# G879X.net
KiCad netlist of a schematic drawn in EAGLE
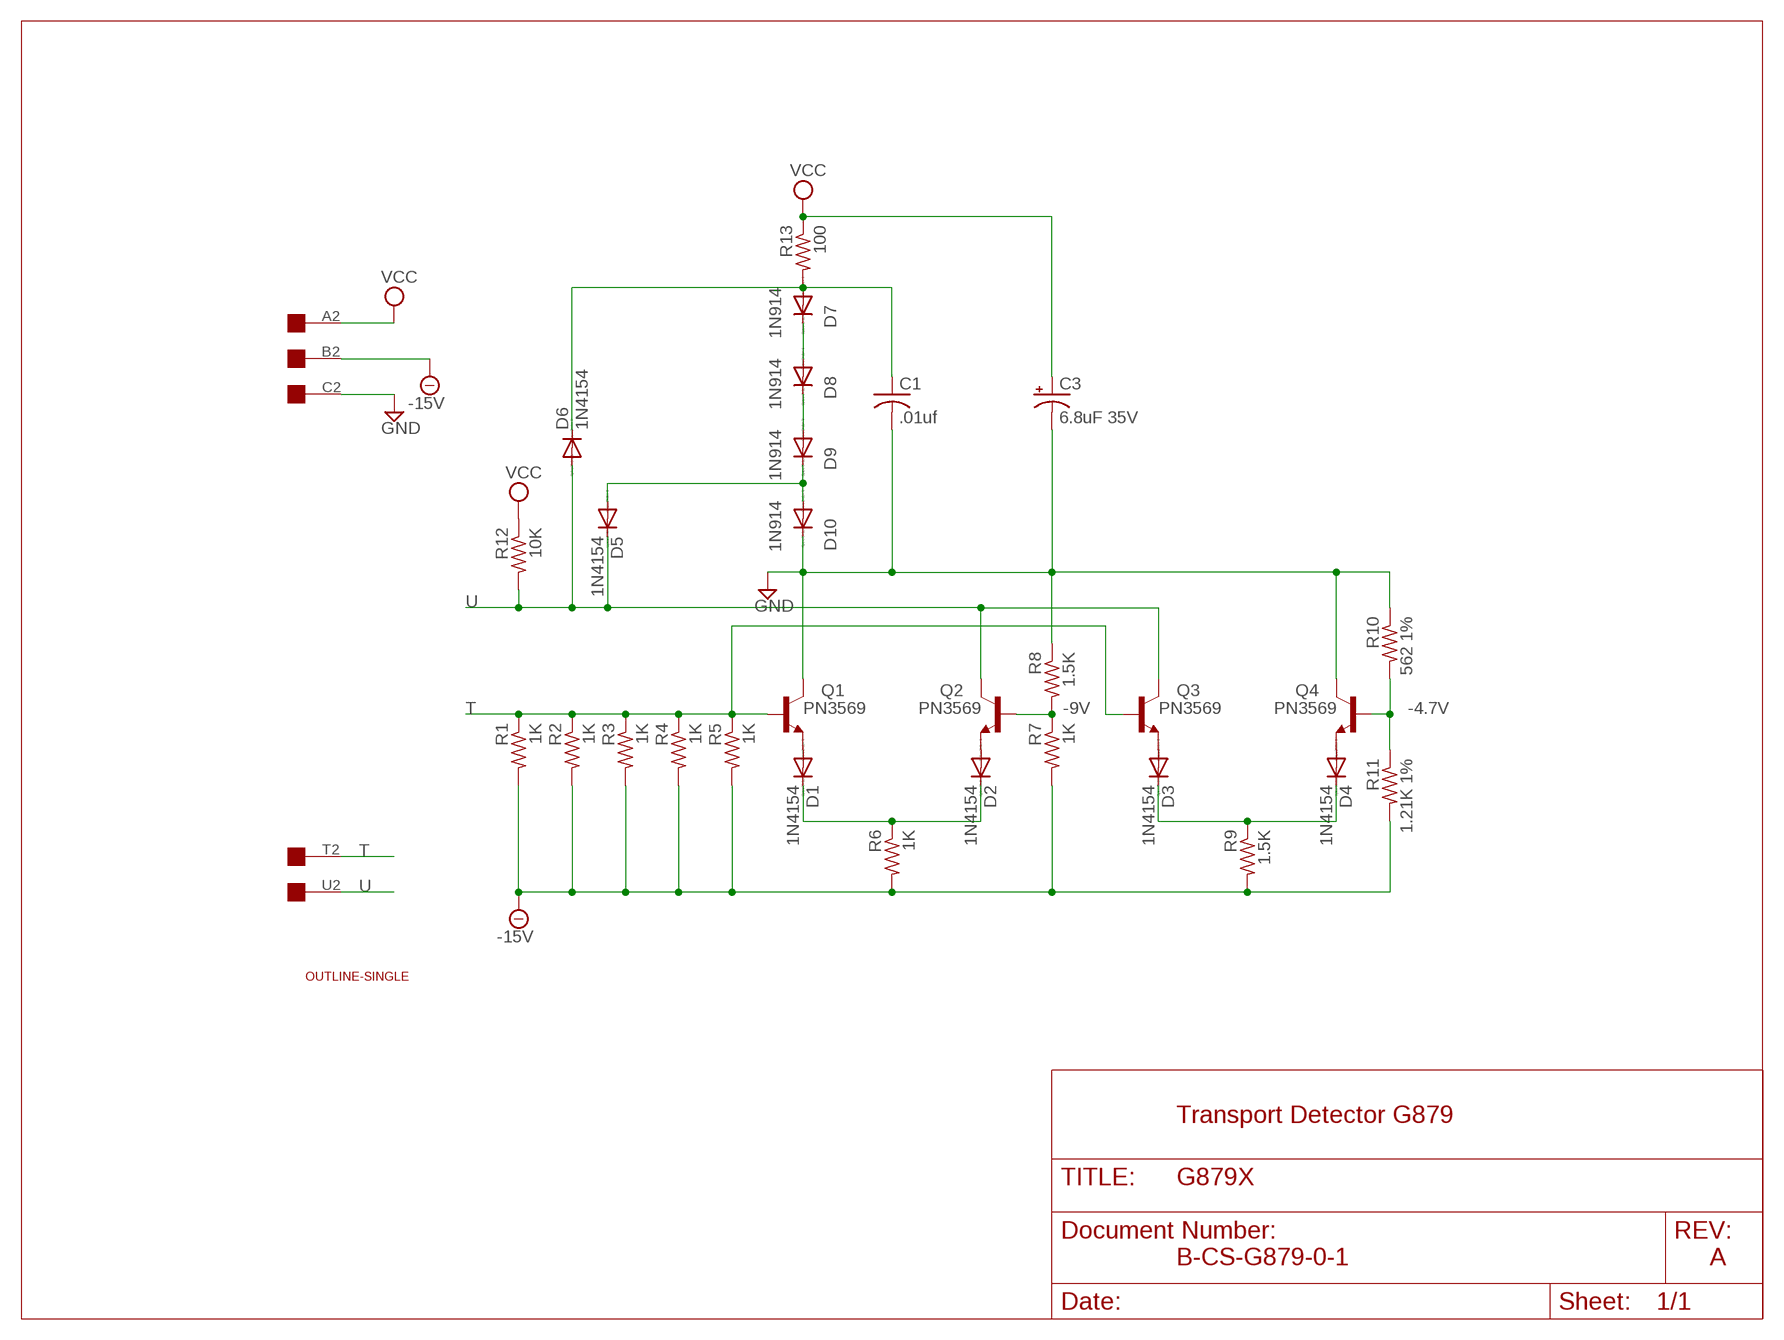
[diagram p0: schematic, sheet 1]

(export (version "E")
  (design (tool "Eeschema 10.0.6"))
  (components
    (comp (ref "C1")
      (value ".01uf")
      (footprint "eagle-import:C050-025X075")
      (libsource (lib "eagle-import") (part "C-US050-025X075"))
    )
    (comp (ref "C3")
      (value "6.8uF 35V")
      (footprint "eagle-import:E12-8")
      (libsource (lib "eagle-import") (part "CPOL-USE20-8AXIAL"))
    )
    (comp (ref "D1")
      (value "1N4154")
      (footprint "eagle-import:DO41-10")
      (libsource (lib "eagle-import") (part "1N4004"))
    )
    (comp (ref "D2")
      (value "1N4154")
      (footprint "eagle-import:DO41-10")
      (libsource (lib "eagle-import") (part "1N4004"))
    )
    (comp (ref "D3")
      (value "1N4154")
      (footprint "eagle-import:DO41-10")
      (libsource (lib "eagle-import") (part "1N4004"))
    )
    (comp (ref "D4")
      (value "1N4154")
      (footprint "eagle-import:DO41-10")
      (libsource (lib "eagle-import") (part "1N4004"))
    )
    (comp (ref "D5")
      (value "1N4154")
      (footprint "eagle-import:DO41-10")
      (libsource (lib "eagle-import") (part "1N4004"))
    )
    (comp (ref "D6")
      (value "1N4154")
      (footprint "eagle-import:DO41-10")
      (libsource (lib "eagle-import") (part "1N4004"))
    )
    (comp (ref "D7")
      (value "1N914")
      (footprint "eagle-import:DO41-10")
      (libsource (lib "eagle-import") (part "1N4004"))
    )
    (comp (ref "D8")
      (value "1N914")
      (footprint "eagle-import:DO41-10")
      (libsource (lib "eagle-import") (part "1N4004"))
    )
    (comp (ref "D9")
      (value "1N914")
      (footprint "eagle-import:DO41-10")
      (libsource (lib "eagle-import") (part "1N4004"))
    )
    (comp (ref "D10")
      (value "1N914")
      (footprint "eagle-import:DO41-10")
      (libsource (lib "eagle-import") (part "1N4004"))
    )
    (comp (ref "Q1")
      (value "PN3569")
      (footprint "eagle-import:TO39")
      (libsource (lib "eagle-import") (part "2N1711"))
    )
    (comp (ref "Q2")
      (value "PN3569")
      (footprint "eagle-import:TO39")
      (libsource (lib "eagle-import") (part "2N1711"))
    )
    (comp (ref "Q3")
      (value "PN3569")
      (footprint "eagle-import:TO39")
      (libsource (lib "eagle-import") (part "2N1711"))
    )
    (comp (ref "Q4")
      (value "PN3569")
      (footprint "eagle-import:TO39")
      (libsource (lib "eagle-import") (part "2N1711"))
    )
    (comp (ref "R1")
      (value "1K")
      (footprint "eagle-import:0207_10")
      (libsource (lib "eagle-import") (part "R-US_0207/10"))
    )
    (comp (ref "R2")
      (value "1K")
      (footprint "eagle-import:0207_10")
      (libsource (lib "eagle-import") (part "R-US_0207/10"))
    )
    (comp (ref "R3")
      (value "1K")
      (footprint "eagle-import:0207_10")
      (libsource (lib "eagle-import") (part "R-US_0207/10"))
    )
    (comp (ref "R4")
      (value "1K")
      (footprint "eagle-import:0207_10")
      (libsource (lib "eagle-import") (part "R-US_0207/10"))
    )
    (comp (ref "R5")
      (value "1K")
      (footprint "eagle-import:0207_10")
      (libsource (lib "eagle-import") (part "R-US_0207/10"))
    )
    (comp (ref "R6")
      (value "1K")
      (footprint "eagle-import:0207_10")
      (libsource (lib "eagle-import") (part "R-US_0207/10"))
    )
    (comp (ref "R7")
      (value "1K")
      (footprint "eagle-import:0207_10")
      (libsource (lib "eagle-import") (part "R-US_0207/10"))
    )
    (comp (ref "R8")
      (value "1.5K")
      (footprint "eagle-import:0207_10")
      (libsource (lib "eagle-import") (part "R-US_0207/10"))
    )
    (comp (ref "R9")
      (value "1.5K")
      (footprint "eagle-import:0207_10")
      (libsource (lib "eagle-import") (part "R-US_0207/10"))
    )
    (comp (ref "R10")
      (value "562 1%")
      (footprint "eagle-import:0207_15")
      (libsource (lib "eagle-import") (part "R-US_0207/15"))
    )
    (comp (ref "R11")
      (value "1.21K 1%")
      (footprint "eagle-import:0207_15")
      (libsource (lib "eagle-import") (part "R-US_0207/15"))
    )
    (comp (ref "R12")
      (value "10K")
      (footprint "eagle-import:0207_10")
      (libsource (lib "eagle-import") (part "R-US_0207/10"))
    )
    (comp (ref "R13")
      (value "100")
      (footprint "eagle-import:0207_10")
      (libsource (lib "eagle-import") (part "R-US_0207/10"))
    )
    (comp (ref "U$1")
      (value "EDGE-1")
      (footprint "eagle-import:EDGE-CON1")
      (libsource (lib "eagle-import") (part "EDGE-1"))
    )
    (comp (ref "U$2")
      (value "OUTLINE-SINGLE")
      (footprint "eagle-import:SINGLE")
      (libsource (lib "eagle-import") (part "OUTLINE-SINGLE"))
    )
  )
  (nets
    (net (code "1") (name "-15V") (class "Default")
      (node (ref "R1") (pin "2") (pinfunction "2_2") (pintype "passive"))
      (node (ref "R11") (pin "2") (pinfunction "2_2") (pintype "passive"))
      (node (ref "R2") (pin "2") (pinfunction "2_2") (pintype "passive"))
      (node (ref "R3") (pin "2") (pinfunction "2_2") (pintype "passive"))
      (node (ref "R4") (pin "2") (pinfunction "2_2") (pintype "passive"))
      (node (ref "R5") (pin "2") (pinfunction "2_2") (pintype "passive"))
      (node (ref "R6") (pin "2") (pinfunction "2_2") (pintype "passive"))
      (node (ref "R7") (pin "2") (pinfunction "2_2") (pintype "passive"))
      (node (ref "R9") (pin "2") (pinfunction "2_2") (pintype "passive"))
      (node (ref "U$1") (pin "B2") (pinfunction "1_B2") (pintype "bidirectional"))
    )
    (net (code "2") (name "/-4.7V") (class "Default")
      (node (ref "Q4") (pin "2") (pinfunction "B_2") (pintype "passive"))
      (node (ref "R10") (pin "2") (pinfunction "2_2") (pintype "passive"))
      (node (ref "R11") (pin "1") (pinfunction "1_1") (pintype "passive"))
    )
    (net (code "3") (name "/-9V") (class "Default")
      (node (ref "Q2") (pin "2") (pinfunction "B_2") (pintype "passive"))
      (node (ref "R7") (pin "1") (pinfunction "1_1") (pintype "passive"))
      (node (ref "R8") (pin "2") (pinfunction "2_2") (pintype "passive"))
    )
    (net (code "4") (name "/T") (class "Default")
      (node (ref "Q1") (pin "2") (pinfunction "B_2") (pintype "passive"))
      (node (ref "Q3") (pin "2") (pinfunction "B_2") (pintype "passive"))
      (node (ref "R1") (pin "1") (pinfunction "1_1") (pintype "passive"))
      (node (ref "R2") (pin "1") (pinfunction "1_1") (pintype "passive"))
      (node (ref "R3") (pin "1") (pinfunction "1_1") (pintype "passive"))
      (node (ref "R4") (pin "1") (pinfunction "1_1") (pintype "passive"))
      (node (ref "R5") (pin "1") (pinfunction "1_1") (pintype "passive"))
      (node (ref "U$1") (pin "T2") (pinfunction "1_T2") (pintype "bidirectional"))
    )
    (net (code "5") (name "/U") (class "Default")
      (node (ref "D5") (pin "C") (pinfunction "C_C") (pintype "passive"))
      (node (ref "D6") (pin "A") (pinfunction "A_A") (pintype "passive"))
      (node (ref "Q2") (pin "3") (pinfunction "C_3") (pintype "passive"))
      (node (ref "Q3") (pin "3") (pinfunction "C_3") (pintype "passive"))
      (node (ref "R12") (pin "2") (pinfunction "2_2") (pintype "passive"))
      (node (ref "U$1") (pin "U2") (pinfunction "1_U2") (pintype "bidirectional"))
    )
    (net (code "6") (name "GND") (class "Default")
      (node (ref "C1") (pin "2") (pinfunction "2_2") (pintype "passive"))
      (node (ref "C3") (pin "-") (pinfunction "-_-") (pintype "passive"))
      (node (ref "D10") (pin "C") (pinfunction "C_C") (pintype "passive"))
      (node (ref "Q1") (pin "3") (pinfunction "C_3") (pintype "passive"))
      (node (ref "Q4") (pin "3") (pinfunction "C_3") (pintype "passive"))
      (node (ref "R10") (pin "1") (pinfunction "1_1") (pintype "passive"))
      (node (ref "R8") (pin "1") (pinfunction "1_1") (pintype "passive"))
      (node (ref "U$1") (pin "C2") (pinfunction "1_C2") (pintype "bidirectional"))
    )
    (net (code "7") (name "Net-(C1-Pad1)") (class "Default")
      (node (ref "C1") (pin "1") (pinfunction "1_1") (pintype "passive"))
      (node (ref "D6") (pin "C") (pinfunction "C_C") (pintype "passive"))
      (node (ref "D7") (pin "A") (pinfunction "A_A") (pintype "passive"))
      (node (ref "R13") (pin "2") (pinfunction "2_2") (pintype "passive"))
    )
    (net (code "8") (name "Net-(D1-PadC)") (class "Default")
      (node (ref "D1") (pin "C") (pinfunction "C_C") (pintype "passive"))
      (node (ref "D2") (pin "C") (pinfunction "C_C") (pintype "passive"))
      (node (ref "R6") (pin "1") (pinfunction "1_1") (pintype "passive"))
    )
    (net (code "9") (name "Net-(D3-PadC)") (class "Default")
      (node (ref "D3") (pin "C") (pinfunction "C_C") (pintype "passive"))
      (node (ref "D4") (pin "C") (pinfunction "C_C") (pintype "passive"))
      (node (ref "R9") (pin "1") (pinfunction "1_1") (pintype "passive"))
    )
    (net (code "10") (name "Net-(D7-PadC)") (class "Default")
      (node (ref "D7") (pin "C") (pinfunction "C_C") (pintype "passive"))
      (node (ref "D8") (pin "A") (pinfunction "A_A") (pintype "passive"))
    )
    (net (code "11") (name "Net-(D8-PadC)") (class "Default")
      (node (ref "D8") (pin "C") (pinfunction "C_C") (pintype "passive"))
      (node (ref "D9") (pin "A") (pinfunction "A_A") (pintype "passive"))
    )
    (net (code "12") (name "Net-(D10-PadA)") (class "Default")
      (node (ref "D10") (pin "A") (pinfunction "A_A") (pintype "passive"))
      (node (ref "D5") (pin "A") (pinfunction "A_A") (pintype "passive"))
      (node (ref "D9") (pin "C") (pinfunction "C_C") (pintype "passive"))
    )
    (net (code "13") (name "Net-(Q1-E)") (class "Default")
      (node (ref "D1") (pin "A") (pinfunction "A_A") (pintype "passive"))
      (node (ref "Q1") (pin "1") (pinfunction "E_1") (pintype "passive"))
    )
    (net (code "14") (name "Net-(Q2-E)") (class "Default")
      (node (ref "D2") (pin "A") (pinfunction "A_A") (pintype "passive"))
      (node (ref "Q2") (pin "1") (pinfunction "E_1") (pintype "passive"))
    )
    (net (code "15") (name "Net-(Q3-E)") (class "Default")
      (node (ref "D3") (pin "A") (pinfunction "A_A") (pintype "passive"))
      (node (ref "Q3") (pin "1") (pinfunction "E_1") (pintype "passive"))
    )
    (net (code "16") (name "Net-(Q4-E)") (class "Default")
      (node (ref "D4") (pin "A") (pinfunction "A_A") (pintype "passive"))
      (node (ref "Q4") (pin "1") (pinfunction "E_1") (pintype "passive"))
    )
    (net (code "17") (name "VCC") (class "Default")
      (node (ref "C3") (pin "+") (pinfunction "+_+") (pintype "passive"))
      (node (ref "R12") (pin "1") (pinfunction "1_1") (pintype "passive"))
      (node (ref "R13") (pin "1") (pinfunction "1_1") (pintype "passive"))
      (node (ref "U$1") (pin "A2") (pinfunction "1_A2") (pintype "bidirectional"))
    )
  )
)
